# Sketchpad.net
KiCad netlist of a schematic drawn in EAGLE
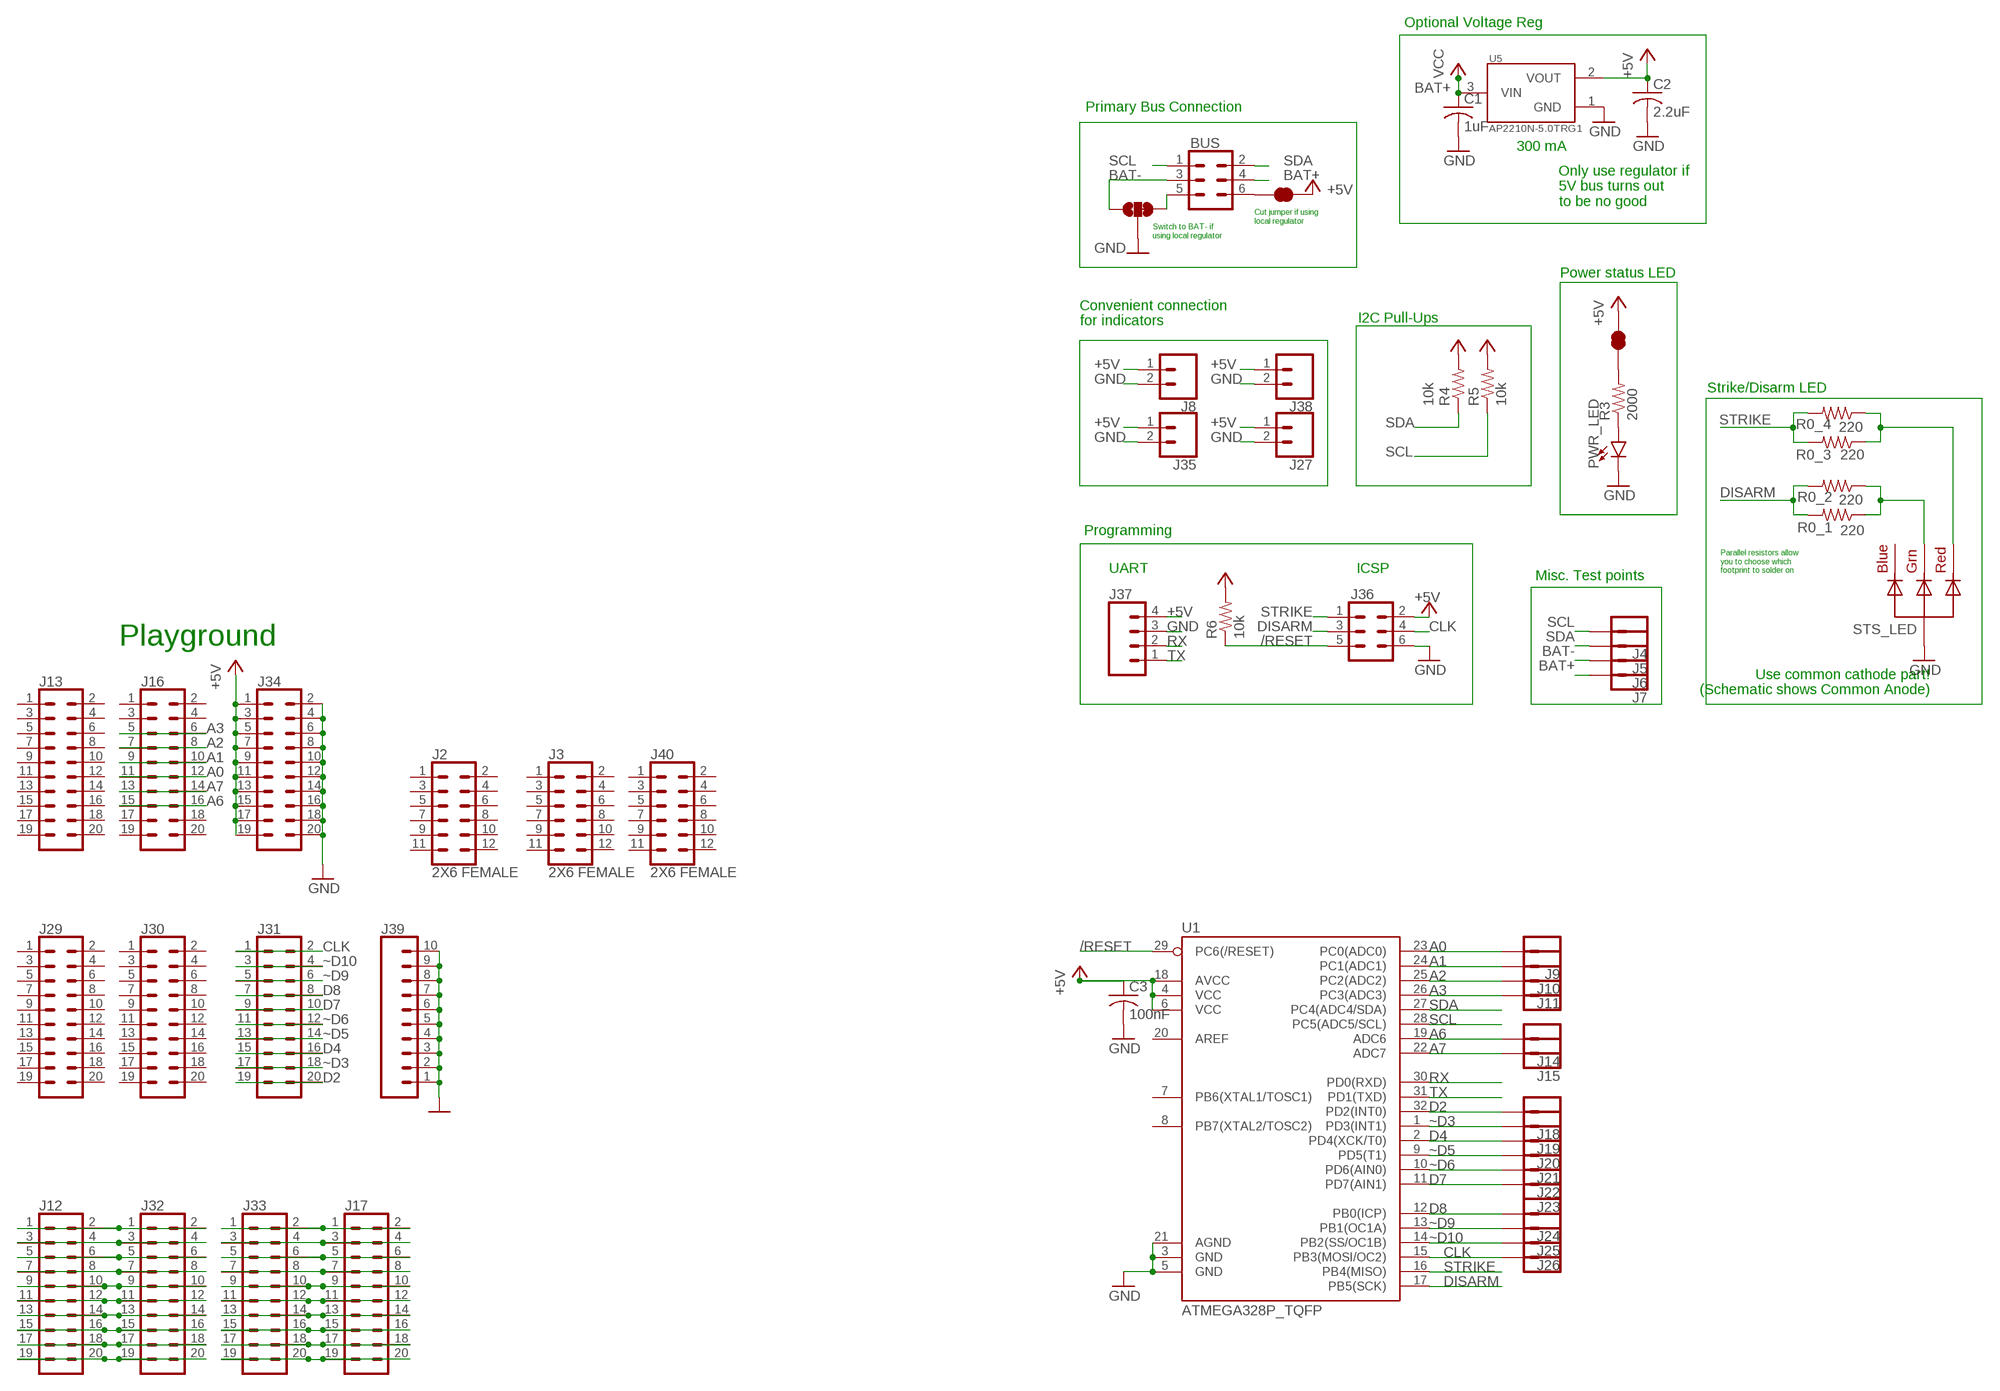
[diagram p0: schematic, sheet 1]

(export (version "E")
  (design (tool "Eeschema 10.0.6"))
  (components
    (comp (ref "BUS")
      (value "CONN_03X2SHROUD")
      (footprint "eagle-import:2X3-SHROUDED")
      (libsource (lib "eagle-import") (part "CONN_03X2SHROUD"))
    )
    (comp (ref "C1")
      (value "1uF")
      (footprint "eagle-import:C0805")
      (libsource (lib "eagle-import") (part "C-USC0805"))
    )
    (comp (ref "C2")
      (value "2.2uF")
      (footprint "eagle-import:C0805")
      (libsource (lib "eagle-import") (part "C-USC0805"))
    )
    (comp (ref "C3")
      (value "100nF")
      (footprint "eagle-import:C0805")
      (libsource (lib "eagle-import") (part "C-USC0805"))
    )
    (comp (ref "J1")
      (value "CONN_01")
      (footprint "eagle-import:1X01")
      (libsource (lib "eagle-import") (part "CONN_01"))
    )
    (comp (ref "J2")
      (value "2X6 FEMALE")
      (footprint "eagle-import:2X6")
      (libsource (lib "eagle-import") (part "CONN_06X2PTH_FEMALE"))
    )
    (comp (ref "J3")
      (value "2X6 FEMALE")
      (footprint "eagle-import:2X6")
      (libsource (lib "eagle-import") (part "CONN_06X2PTH_FEMALE"))
    )
    (comp (ref "J4")
      (value "CONN_01")
      (footprint "eagle-import:1X01")
      (libsource (lib "eagle-import") (part "CONN_01"))
    )
    (comp (ref "J5")
      (value "CONN_01")
      (footprint "eagle-import:1X01")
      (libsource (lib "eagle-import") (part "CONN_01"))
    )
    (comp (ref "J6")
      (value "CONN_01")
      (footprint "eagle-import:1X01")
      (libsource (lib "eagle-import") (part "CONN_01"))
    )
    (comp (ref "J7")
      (value "CONN_01")
      (footprint "eagle-import:1X01")
      (libsource (lib "eagle-import") (part "CONN_01"))
    )
    (comp (ref "J8")
      (value "CONN_02POLAR")
      (footprint "eagle-import:MOLEX-1X2")
      (libsource (lib "eagle-import") (part "CONN_02POLAR"))
    )
    (comp (ref "J9")
      (value "CONN_01")
      (footprint "eagle-import:1X01")
      (libsource (lib "eagle-import") (part "CONN_01"))
    )
    (comp (ref "J10")
      (value "CONN_01")
      (footprint "eagle-import:1X01")
      (libsource (lib "eagle-import") (part "CONN_01"))
    )
    (comp (ref "J11")
      (value "CONN_01")
      (footprint "eagle-import:1X01")
      (libsource (lib "eagle-import") (part "CONN_01"))
    )
    (comp (ref "J12")
      (value "CONN_10X2NOSILK")
      (footprint "eagle-import:2X10_NOSILK")
      (libsource (lib "eagle-import") (part "CONN_10X2NOSILK"))
    )
    (comp (ref "J13")
      (value "CONN_10X2NOSILK")
      (footprint "eagle-import:2X10_NOSILK")
      (libsource (lib "eagle-import") (part "CONN_10X2NOSILK"))
    )
    (comp (ref "J14")
      (value "CONN_01")
      (footprint "eagle-import:1X01")
      (libsource (lib "eagle-import") (part "CONN_01"))
    )
    (comp (ref "J15")
      (value "CONN_01")
      (footprint "eagle-import:1X01")
      (libsource (lib "eagle-import") (part "CONN_01"))
    )
    (comp (ref "J16")
      (value "CONN_10X2NOSILK")
      (footprint "eagle-import:2X10_NOSILK")
      (libsource (lib "eagle-import") (part "CONN_10X2NOSILK"))
    )
    (comp (ref "J17")
      (value "CONN_10X2NOSILK")
      (footprint "eagle-import:2X10_NOSILK")
      (libsource (lib "eagle-import") (part "CONN_10X2NOSILK"))
    )
    (comp (ref "J18")
      (value "CONN_01")
      (footprint "eagle-import:1X01")
      (libsource (lib "eagle-import") (part "CONN_01"))
    )
    (comp (ref "J19")
      (value "CONN_01")
      (footprint "eagle-import:1X01")
      (libsource (lib "eagle-import") (part "CONN_01"))
    )
    (comp (ref "J20")
      (value "CONN_01")
      (footprint "eagle-import:1X01")
      (libsource (lib "eagle-import") (part "CONN_01"))
    )
    (comp (ref "J21")
      (value "CONN_01")
      (footprint "eagle-import:1X01")
      (libsource (lib "eagle-import") (part "CONN_01"))
    )
    (comp (ref "J22")
      (value "CONN_01")
      (footprint "eagle-import:1X01")
      (libsource (lib "eagle-import") (part "CONN_01"))
    )
    (comp (ref "J23")
      (value "CONN_01")
      (footprint "eagle-import:1X01")
      (libsource (lib "eagle-import") (part "CONN_01"))
    )
    (comp (ref "J24")
      (value "CONN_01")
      (footprint "eagle-import:1X01")
      (libsource (lib "eagle-import") (part "CONN_01"))
    )
    (comp (ref "J25")
      (value "CONN_01")
      (footprint "eagle-import:1X01")
      (libsource (lib "eagle-import") (part "CONN_01"))
    )
    (comp (ref "J26")
      (value "CONN_01")
      (footprint "eagle-import:1X01")
      (libsource (lib "eagle-import") (part "CONN_01"))
    )
    (comp (ref "J27")
      (value "CONN_02POLAR")
      (footprint "eagle-import:MOLEX-1X2")
      (libsource (lib "eagle-import") (part "CONN_02POLAR"))
    )
    (comp (ref "J28")
      (value "CONN_01")
      (footprint "eagle-import:1X01")
      (libsource (lib "eagle-import") (part "CONN_01"))
    )
    (comp (ref "J29")
      (value "CONN_10X2NOSILK")
      (footprint "eagle-import:2X10_NOSILK")
      (libsource (lib "eagle-import") (part "CONN_10X2NOSILK"))
    )
    (comp (ref "J30")
      (value "CONN_10X2NOSILK")
      (footprint "eagle-import:2X10_NOSILK")
      (libsource (lib "eagle-import") (part "CONN_10X2NOSILK"))
    )
    (comp (ref "J31")
      (value "CONN_10X2NOSILK")
      (footprint "eagle-import:2X10_NOSILK")
      (libsource (lib "eagle-import") (part "CONN_10X2NOSILK"))
    )
    (comp (ref "J32")
      (value "CONN_10X2NOSILK")
      (footprint "eagle-import:2X10_NOSILK")
      (libsource (lib "eagle-import") (part "CONN_10X2NOSILK"))
    )
    (comp (ref "J33")
      (value "CONN_10X2NOSILK")
      (footprint "eagle-import:2X10_NOSILK")
      (libsource (lib "eagle-import") (part "CONN_10X2NOSILK"))
    )
    (comp (ref "J34")
      (value "CONN_10X2NOSILK")
      (footprint "eagle-import:2X10_NOSILK")
      (libsource (lib "eagle-import") (part "CONN_10X2NOSILK"))
    )
    (comp (ref "J35")
      (value "CONN_02POLAR")
      (footprint "eagle-import:MOLEX-1X2")
      (libsource (lib "eagle-import") (part "CONN_02POLAR"))
    )
    (comp (ref "J36")
      (value "CONN_03X22X3_SILK_MALE_PTH")
      (footprint "eagle-import:2X3")
      (libsource (lib "eagle-import") (part "CONN_03X22X3_SILK_MALE_PTH"))
    )
    (comp (ref "J37")
      (value "CONN_04")
      (footprint "eagle-import:1X04")
      (libsource (lib "eagle-import") (part "CONN_04"))
    )
    (comp (ref "J38")
      (value "CONN_02POLAR")
      (footprint "eagle-import:MOLEX-1X2")
      (libsource (lib "eagle-import") (part "CONN_02POLAR"))
    )
    (comp (ref "J39")
      (value "CONN_10NO_SILK_PTH_FEMALE")
      (footprint "eagle-import:1X10_NO_SILK")
      (libsource (lib "eagle-import") (part "CONN_10NO_SILK_PTH_FEMALE"))
    )
    (comp (ref "J40")
      (value "2X6 FEMALE")
      (footprint "eagle-import:2X6")
      (libsource (lib "eagle-import") (part "CONN_06X2PTH_FEMALE"))
    )
    (comp (ref "JP1")
      (value "JUMPER-SMT_2_NC_TRACE_SILK")
      (footprint "eagle-import:SMT-JUMPER_2_NC_TRACE_SILK")
      (libsource (lib "eagle-import") (part "JUMPER-SMT_2_NC_TRACE_SILK"))
    )
    (comp (ref "JP2")
      (value "JUMPER-SMT_3_1-NC_TRACE_SILK")
      (footprint "eagle-import:SMT-JUMPER_3_1-NC_TRACE_SILK")
      (libsource (lib "eagle-import") (part "JUMPER-SMT_3_1-NC_TRACE_SILK"))
    )
    (comp (ref "JP3")
      (value "JUMPER-SMT_2_NC_TRACE_SILK")
      (footprint "eagle-import:SMT-JUMPER_2_NC_TRACE_SILK")
      (libsource (lib "eagle-import") (part "JUMPER-SMT_2_NC_TRACE_SILK"))
    )
    (comp (ref "PWR_LED")
      (value "LED3MM")
      (footprint "eagle-import:LED_3MM")
      (libsource (lib "eagle-import") (part "LED3MM"))
    )
    (comp (ref "R0_1")
      (value "220")
      (footprint "eagle-import:0204_7")
      (libsource (lib "eagle-import") (part "R-US_0204/7"))
    )
    (comp (ref "R0_2")
      (value "220")
      (footprint "eagle-import:R0805")
      (libsource (lib "eagle-import") (part "R-US_R0805"))
    )
    (comp (ref "R0_3")
      (value "220")
      (footprint "eagle-import:0204_7")
      (libsource (lib "eagle-import") (part "R-US_0204/7"))
    )
    (comp (ref "R0_4")
      (value "220")
      (footprint "eagle-import:R0805")
      (libsource (lib "eagle-import") (part "R-US_R0805"))
    )
    (comp (ref "R3")
      (value "2000")
      (footprint "eagle-import:0204_7")
      (libsource (lib "eagle-import") (part "R-US_0204/7"))
    )
    (comp (ref "R4")
      (value "10k")
      (footprint "eagle-import:0204_7")
      (libsource (lib "eagle-import") (part "R-US_0204/7"))
    )
    (comp (ref "R5")
      (value "10k")
      (footprint "eagle-import:0204_7")
      (libsource (lib "eagle-import") (part "R-US_0204/7"))
    )
    (comp (ref "R6")
      (value "10k")
      (footprint "eagle-import:0204_7")
      (libsource (lib "eagle-import") (part "R-US_0204/7"))
    )
    (comp (ref "STS_LED")
      (value "RGBLED_CA-5MM")
      (footprint "eagle-import:LED5MMRGB")
      (libsource (lib "eagle-import") (part "RGBLED_CA-5MM"))
    )
    (comp (ref "U1")
      (value "ATMEGA328P_TQFP")
      (footprint "eagle-import:TQFP32-08")
      (libsource (lib "eagle-import") (part "ATMEGA328P_TQFP"))
    )
    (comp (ref "U5")
      (value "AP2210N-5.0TRG1")
      (footprint "eagle-import:SOT95P280X145-3N")
      (fields
        (field (name "DIGI-KEY_PART_NUMBER") "AP2210N-5.0TRG1DICT-ND")
        (field (name "MF") "Diodes Inc.")
      )
      (libsource (lib "eagle-import") (part "AP2210N-5.0TRG1"))
    )
  )
  (nets
    (net (code "1") (name "+5V") (class "Default")
      (node (ref "C2") (pin "1") (pinfunction "1_1") (pintype "passive"))
      (node (ref "C3") (pin "1") (pinfunction "1_1") (pintype "passive"))
      (node (ref "J27") (pin "1") (pinfunction "1_1") (pintype "passive"))
      (node (ref "J34") (pin "1") (pinfunction "1_1") (pintype "passive"))
      (node (ref "J34") (pin "11") (pinfunction "11_11") (pintype "passive"))
      (node (ref "J34") (pin "13") (pinfunction "13_13") (pintype "passive"))
      (node (ref "J34") (pin "15") (pinfunction "15_15") (pintype "passive"))
      (node (ref "J34") (pin "17") (pinfunction "17_17") (pintype "passive"))
      (node (ref "J34") (pin "19") (pinfunction "19_19") (pintype "passive"))
      (node (ref "J34") (pin "3") (pinfunction "3_3") (pintype "passive"))
      (node (ref "J34") (pin "5") (pinfunction "5_5") (pintype "passive"))
      (node (ref "J34") (pin "7") (pinfunction "7_7") (pintype "passive"))
      (node (ref "J34") (pin "9") (pinfunction "9_9") (pintype "passive"))
      (node (ref "J35") (pin "1") (pinfunction "1_1") (pintype "passive"))
      (node (ref "J36") (pin "2") (pinfunction "2_2") (pintype "bidirectional"))
      (node (ref "J37") (pin "4") (pinfunction "4_4") (pintype "passive"))
      (node (ref "J38") (pin "1") (pinfunction "1_1") (pintype "passive"))
      (node (ref "J8") (pin "1") (pinfunction "1_1") (pintype "passive"))
      (node (ref "JP1") (pin "2") (pinfunction "2_2") (pintype "passive"))
      (node (ref "JP3") (pin "2") (pinfunction "2_2") (pintype "passive"))
      (node (ref "R4") (pin "2") (pinfunction "2_2") (pintype "passive"))
      (node (ref "R5") (pin "2") (pinfunction "2_2") (pintype "passive"))
      (node (ref "R6") (pin "2") (pinfunction "2_2") (pintype "passive"))
      (node (ref "U1") (pin "18") (pinfunction "AVCC_18") (pintype "bidirectional"))
      (node (ref "U1") (pin "4") (pinfunction "VCC_4") (pintype "bidirectional"))
      (node (ref "U1") (pin "6") (pinfunction "VCC_6") (pintype "bidirectional"))
      (node (ref "U5") (pin "2") (pinfunction "VOUT_2") (pintype "output"))
    )
    (net (code "2") (name "/A0") (class "Default")
      (node (ref "J16") (pin "11") (pinfunction "11_11") (pintype "passive"))
      (node (ref "J16") (pin "12") (pinfunction "12_12") (pintype "passive"))
      (node (ref "J9") (pin "1") (pinfunction "1_1") (pintype "passive"))
      (node (ref "U1") (pin "23") (pinfunction "PC0(ADC0)_23") (pintype "bidirectional"))
    )
    (net (code "3") (name "/A1") (class "Default")
      (node (ref "J10") (pin "1") (pinfunction "1_1") (pintype "passive"))
      (node (ref "J16") (pin "10") (pinfunction "10_10") (pintype "passive"))
      (node (ref "J16") (pin "9") (pinfunction "9_9") (pintype "passive"))
      (node (ref "U1") (pin "24") (pinfunction "PC1(ADC1)_24") (pintype "bidirectional"))
    )
    (net (code "4") (name "/A2") (class "Default")
      (node (ref "J11") (pin "1") (pinfunction "1_1") (pintype "passive"))
      (node (ref "J16") (pin "7") (pinfunction "7_7") (pintype "passive"))
      (node (ref "J16") (pin "8") (pinfunction "8_8") (pintype "passive"))
      (node (ref "U1") (pin "25") (pinfunction "PC2(ADC2)_25") (pintype "bidirectional"))
    )
    (net (code "5") (name "/A3") (class "Default")
      (node (ref "J16") (pin "5") (pinfunction "5_5") (pintype "passive"))
      (node (ref "J16") (pin "6") (pinfunction "6_6") (pintype "passive"))
      (node (ref "J28") (pin "1") (pinfunction "1_1") (pintype "passive"))
      (node (ref "U1") (pin "26") (pinfunction "PC3(ADC3)_26") (pintype "bidirectional"))
    )
    (net (code "6") (name "/A6") (class "Default")
      (node (ref "J14") (pin "1") (pinfunction "1_1") (pintype "passive"))
      (node (ref "J16") (pin "15") (pinfunction "15_15") (pintype "passive"))
      (node (ref "J16") (pin "16") (pinfunction "16_16") (pintype "passive"))
      (node (ref "U1") (pin "19") (pinfunction "ADC6_19") (pintype "bidirectional"))
    )
    (net (code "7") (name "/A7") (class "Default")
      (node (ref "J15") (pin "1") (pinfunction "1_1") (pintype "passive"))
      (node (ref "J16") (pin "13") (pinfunction "13_13") (pintype "passive"))
      (node (ref "J16") (pin "14") (pinfunction "14_14") (pintype "passive"))
      (node (ref "U1") (pin "22") (pinfunction "ADC7_22") (pintype "bidirectional"))
    )
    (net (code "8") (name "/BAT-") (class "Default")
      (node (ref "BUS") (pin "3") (pinfunction "3_3") (pintype "bidirectional"))
      (node (ref "J6") (pin "1") (pinfunction "1_1") (pintype "passive"))
      (node (ref "JP2") (pin "1") (pinfunction "1_1") (pintype "passive"))
    )
    (net (code "9") (name "/CLK") (class "Default")
      (node (ref "J1") (pin "1") (pinfunction "1_1") (pintype "passive"))
      (node (ref "J31") (pin "1") (pinfunction "1_1") (pintype "passive"))
      (node (ref "J31") (pin "2") (pinfunction "2_2") (pintype "passive"))
      (node (ref "J36") (pin "4") (pinfunction "4_4") (pintype "bidirectional"))
      (node (ref "U1") (pin "15") (pinfunction "PB3(MOSI/OC2)_15") (pintype "bidirectional"))
    )
    (net (code "10") (name "/D2") (class "Default")
      (node (ref "J18") (pin "1") (pinfunction "1_1") (pintype "passive"))
      (node (ref "J31") (pin "19") (pinfunction "19_19") (pintype "passive"))
      (node (ref "J31") (pin "20") (pinfunction "20_20") (pintype "passive"))
      (node (ref "U1") (pin "32") (pinfunction "PD2(INT0)_32") (pintype "bidirectional"))
    )
    (net (code "11") (name "/D4") (class "Default")
      (node (ref "J20") (pin "1") (pinfunction "1_1") (pintype "passive"))
      (node (ref "J31") (pin "15") (pinfunction "15_15") (pintype "passive"))
      (node (ref "J31") (pin "16") (pinfunction "16_16") (pintype "passive"))
      (node (ref "U1") (pin "2") (pinfunction "PD4(XCK/T0)_2") (pintype "bidirectional"))
    )
    (net (code "12") (name "/D7") (class "Default")
      (node (ref "J23") (pin "1") (pinfunction "1_1") (pintype "passive"))
      (node (ref "J31") (pin "10") (pinfunction "10_10") (pintype "passive"))
      (node (ref "J31") (pin "9") (pinfunction "9_9") (pintype "passive"))
      (node (ref "U1") (pin "11") (pinfunction "PD7(AIN1)_11") (pintype "bidirectional"))
    )
    (net (code "13") (name "/D8") (class "Default")
      (node (ref "J24") (pin "1") (pinfunction "1_1") (pintype "passive"))
      (node (ref "J31") (pin "7") (pinfunction "7_7") (pintype "passive"))
      (node (ref "J31") (pin "8") (pinfunction "8_8") (pintype "passive"))
      (node (ref "U1") (pin "12") (pinfunction "PB0(ICP)_12") (pintype "bidirectional"))
    )
    (net (code "14") (name "/DISARM") (class "Default")
      (node (ref "J36") (pin "3") (pinfunction "3_3") (pintype "bidirectional"))
      (node (ref "R0_1") (pin "2") (pinfunction "2_2") (pintype "passive"))
      (node (ref "R0_2") (pin "2") (pinfunction "2_2") (pintype "passive"))
      (node (ref "U1") (pin "17") (pinfunction "PB5(SCK)_17") (pintype "bidirectional"))
    )
    (net (code "15") (name "/RX") (class "Default")
      (node (ref "J37") (pin "2") (pinfunction "2_2") (pintype "passive"))
      (node (ref "U1") (pin "30") (pinfunction "PD0(RXD)_30") (pintype "bidirectional"))
    )
    (net (code "16") (name "/SCL") (class "Default")
      (node (ref "BUS") (pin "1") (pinfunction "1_1") (pintype "bidirectional"))
      (node (ref "J4") (pin "1") (pinfunction "1_1") (pintype "passive"))
      (node (ref "R5") (pin "1") (pinfunction "1_1") (pintype "passive"))
      (node (ref "U1") (pin "28") (pinfunction "PC5(ADC5/SCL)_28") (pintype "bidirectional"))
    )
    (net (code "17") (name "/SDA") (class "Default")
      (node (ref "BUS") (pin "2") (pinfunction "2_2") (pintype "bidirectional"))
      (node (ref "J5") (pin "1") (pinfunction "1_1") (pintype "passive"))
      (node (ref "R4") (pin "1") (pinfunction "1_1") (pintype "passive"))
      (node (ref "U1") (pin "27") (pinfunction "PC4(ADC4/SDA)_27") (pintype "bidirectional"))
    )
    (net (code "18") (name "/STRIKE") (class "Default")
      (node (ref "J36") (pin "1") (pinfunction "1_1") (pintype "bidirectional"))
      (node (ref "R0_3") (pin "2") (pinfunction "2_2") (pintype "passive"))
      (node (ref "R0_4") (pin "2") (pinfunction "2_2") (pintype "passive"))
      (node (ref "U1") (pin "16") (pinfunction "PB4(MISO)_16") (pintype "bidirectional"))
    )
    (net (code "19") (name "/TX") (class "Default")
      (node (ref "J37") (pin "1") (pinfunction "1_1") (pintype "passive"))
      (node (ref "U1") (pin "31") (pinfunction "PD1(TXD)_31") (pintype "bidirectional"))
    )
    (net (code "20") (name "/{slash}RESET") (class "Default")
      (node (ref "J36") (pin "5") (pinfunction "5_5") (pintype "bidirectional"))
      (node (ref "R6") (pin "1") (pinfunction "1_1") (pintype "passive"))
      (node (ref "U1") (pin "29") (pinfunction "PC6(/RESET)_29") (pintype "bidirectional"))
    )
    (net (code "21") (name "/~{D3}") (class "Default")
      (node (ref "J19") (pin "1") (pinfunction "1_1") (pintype "passive"))
      (node (ref "J31") (pin "17") (pinfunction "17_17") (pintype "passive"))
      (node (ref "J31") (pin "18") (pinfunction "18_18") (pintype "passive"))
      (node (ref "U1") (pin "1") (pinfunction "PD3(INT1)_1") (pintype "bidirectional"))
    )
    (net (code "22") (name "/~{D5}") (class "Default")
      (node (ref "J21") (pin "1") (pinfunction "1_1") (pintype "passive"))
      (node (ref "J31") (pin "13") (pinfunction "13_13") (pintype "passive"))
      (node (ref "J31") (pin "14") (pinfunction "14_14") (pintype "passive"))
      (node (ref "U1") (pin "9") (pinfunction "PD5(T1)_9") (pintype "bidirectional"))
    )
    (net (code "23") (name "/~{D6}") (class "Default")
      (node (ref "J22") (pin "1") (pinfunction "1_1") (pintype "passive"))
      (node (ref "J31") (pin "11") (pinfunction "11_11") (pintype "passive"))
      (node (ref "J31") (pin "12") (pinfunction "12_12") (pintype "passive"))
      (node (ref "U1") (pin "10") (pinfunction "PD6(AIN0)_10") (pintype "bidirectional"))
    )
    (net (code "24") (name "/~{D9}") (class "Default")
      (node (ref "J25") (pin "1") (pinfunction "1_1") (pintype "passive"))
      (node (ref "J31") (pin "5") (pinfunction "5_5") (pintype "passive"))
      (node (ref "J31") (pin "6") (pinfunction "6_6") (pintype "passive"))
      (node (ref "U1") (pin "13") (pinfunction "PB1(OC1A)_13") (pintype "bidirectional"))
    )
    (net (code "25") (name "/~{D10}") (class "Default")
      (node (ref "J26") (pin "1") (pinfunction "1_1") (pintype "passive"))
      (node (ref "J31") (pin "3") (pinfunction "3_3") (pintype "passive"))
      (node (ref "J31") (pin "4") (pinfunction "4_4") (pintype "passive"))
      (node (ref "U1") (pin "14") (pinfunction "PB2(SS/OC1B)_14") (pintype "bidirectional"))
    )
    (net (code "26") (name "GND") (class "Default")
      (node (ref "C1") (pin "2") (pinfunction "2_2") (pintype "passive"))
      (node (ref "C2") (pin "2") (pinfunction "2_2") (pintype "passive"))
      (node (ref "C3") (pin "2") (pinfunction "2_2") (pintype "passive"))
      (node (ref "J27") (pin "2") (pinfunction "2_2") (pintype "passive"))
      (node (ref "J34") (pin "10") (pinfunction "10_10") (pintype "passive"))
      (node (ref "J34") (pin "12") (pinfunction "12_12") (pintype "passive"))
      (node (ref "J34") (pin "14") (pinfunction "14_14") (pintype "passive"))
      (node (ref "J34") (pin "16") (pinfunction "16_16") (pintype "passive"))
      (node (ref "J34") (pin "18") (pinfunction "18_18") (pintype "passive"))
      (node (ref "J34") (pin "2") (pinfunction "2_2") (pintype "passive"))
      (node (ref "J34") (pin "20") (pinfunction "20_20") (pintype "passive"))
      (node (ref "J34") (pin "4") (pinfunction "4_4") (pintype "passive"))
      (node (ref "J34") (pin "6") (pinfunction "6_6") (pintype "passive"))
      (node (ref "J34") (pin "8") (pinfunction "8_8") (pintype "passive"))
      (node (ref "J35") (pin "2") (pinfunction "2_2") (pintype "passive"))
      (node (ref "J36") (pin "6") (pinfunction "6_6") (pintype "bidirectional"))
      (node (ref "J37") (pin "3") (pinfunction "3_3") (pintype "passive"))
      (node (ref "J38") (pin "2") (pinfunction "2_2") (pintype "passive"))
      (node (ref "J39") (pin "1") (pinfunction "1_1") (pintype "passive"))
      (node (ref "J39") (pin "10") (pinfunction "10_10") (pintype "passive"))
      (node (ref "J39") (pin "2") (pinfunction "2_2") (pintype "passive"))
      (node (ref "J39") (pin "3") (pinfunction "3_3") (pintype "passive"))
      (node (ref "J39") (pin "4") (pinfunction "4_4") (pintype "passive"))
      (node (ref "J39") (pin "5") (pinfunction "5_5") (pintype "passive"))
      (node (ref "J39") (pin "6") (pinfunction "6_6") (pintype "passive"))
      (node (ref "J39") (pin "7") (pinfunction "7_7") (pintype "passive"))
      (node (ref "J39") (pin "8") (pinfunction "8_8") (pintype "passive"))
      (node (ref "J39") (pin "9") (pinfunction "9_9") (pintype "passive"))
      (node (ref "J8") (pin "2") (pinfunction "2_2") (pintype "passive"))
      (node (ref "JP2") (pin "2") (pinfunction "2_2") (pintype "passive"))
      (node (ref "PWR_LED") (pin "K") (pinfunction "C_K") (pintype "passive"))
      (node (ref "STS_LED") (pin "2") (pinfunction "VCC_2") (pintype "bidirectional"))
      (node (ref "U1") (pin "21") (pinfunction "AGND_21") (pintype "bidirectional"))
      (node (ref "U1") (pin "3") (pinfunction "GND_3") (pintype "bidirectional"))
      (node (ref "U1") (pin "5") (pinfunction "GND_5") (pintype "bidirectional"))
      (node (ref "U5") (pin "1") (pinfunction "GND_1") (pintype "power_in"))
    )
    (net (code "27") (name "Net-(BUS-Pad5)") (class "Default")
      (node (ref "BUS") (pin "5") (pinfunction "5_5") (pintype "bidirectional"))
      (node (ref "JP2") (pin "3") (pinfunction "3_3") (pintype "passive"))
    )
    (net (code "28") (name "Net-(BUS-Pad6)") (class "Default")
      (node (ref "BUS") (pin "6") (pinfunction "6_6") (pintype "bidirectional"))
      (node (ref "JP1") (pin "1") (pinfunction "1_1") (pintype "passive"))
    )
    (net (code "29") (name "Net-(J12-Pad1)") (class "Default")
      (node (ref "J12") (pin "1") (pinfunction "1_1") (pintype "passive"))
      (node (ref "J12") (pin "2") (pinfunction "2_2") (pintype "passive"))
      (node (ref "J32") (pin "1") (pinfunction "1_1") (pintype "passive"))
      (node (ref "J32") (pin "2") (pinfunction "2_2") (pintype "passive"))
    )
    (net (code "30") (name "Net-(J12-Pad3)") (class "Default")
      (node (ref "J12") (pin "3") (pinfunction "3_3") (pintype "passive"))
      (node (ref "J12") (pin "4") (pinfunction "4_4") (pintype "passive"))
      (node (ref "J32") (pin "3") (pinfunction "3_3") (pintype "passive"))
      (node (ref "J32") (pin "4") (pinfunction "4_4") (pintype "passive"))
    )
    (net (code "31") (name "Net-(J12-Pad5)") (class "Default")
      (node (ref "J12") (pin "5") (pinfunction "5_5") (pintype "passive"))
      (node (ref "J12") (pin "6") (pinfunction "6_6") (pintype "passive"))
      (node (ref "J32") (pin "5") (pinfunction "5_5") (pintype "passive"))
      (node (ref "J32") (pin "6") (pinfunction "6_6") (pintype "passive"))
    )
    (net (code "32") (name "Net-(J12-Pad7)") (class "Default")
      (node (ref "J12") (pin "7") (pinfunction "7_7") (pintype "passive"))
      (node (ref "J12") (pin "8") (pinfunction "8_8") (pintype "passive"))
      (node (ref "J32") (pin "7") (pinfunction "7_7") (pintype "passive"))
      (node (ref "J32") (pin "8") (pinfunction "8_8") (pintype "passive"))
    )
    (net (code "33") (name "Net-(J12-Pad10)") (class "Default")
      (node (ref "J12") (pin "10") (pinfunction "10_10") (pintype "passive"))
      (node (ref "J12") (pin "9") (pinfunction "9_9") (pintype "passive"))
      (node (ref "J32") (pin "10") (pinfunction "10_10") (pintype "passive"))
      (node (ref "J32") (pin "9") (pinfunction "9_9") (pintype "passive"))
    )
    (net (code "34") (name "Net-(J12-Pad11)") (class "Default")
      (node (ref "J12") (pin "11") (pinfunction "11_11") (pintype "passive"))
      (node (ref "J12") (pin "12") (pinfunction "12_12") (pintype "passive"))
      (node (ref "J32") (pin "11") (pinfunction "11_11") (pintype "passive"))
      (node (ref "J32") (pin "12") (pinfunction "12_12") (pintype "passive"))
    )
    (net (code "35") (name "Net-(J12-Pad13)") (class "Default")
      (node (ref "J12") (pin "13") (pinfunction "13_13") (pintype "passive"))
      (node (ref "J12") (pin "14") (pinfunction "14_14") (pintype "passive"))
      (node (ref "J32") (pin "13") (pinfunction "13_13") (pintype "passive"))
      (node (ref "J32") (pin "14") (pinfunction "14_14") (pintype "passive"))
    )
    (net (code "36") (name "Net-(J12-Pad15)") (class "Default")
      (node (ref "J12") (pin "15") (pinfunction "15_15") (pintype "passive"))
      (node (ref "J12") (pin "16") (pinfunction "16_16") (pintype "passive"))
      (node (ref "J32") (pin "15") (pinfunction "15_15") (pintype "passive"))
      (node (ref "J32") (pin "16") (pinfunction "16_16") (pintype "passive"))
    )
    (net (code "37") (name "Net-(J12-Pad17)") (class "Default")
      (node (ref "J12") (pin "17") (pinfunction "17_17") (pintype "passive"))
      (node (ref "J12") (pin "18") (pinfunction "18_18") (pintype "passive"))
      (node (ref "J32") (pin "17") (pinfunction "17_17") (pintype "passive"))
      (node (ref "J32") (pin "18") (pinfunction "18_18") (pintype "passive"))
    )
    (net (code "38") (name "Net-(J12-Pad19)") (class "Default")
      (node (ref "J12") (pin "19") (pinfunction "19_19") (pintype "passive"))
      (node (ref "J12") (pin "20") (pinfunction "20_20") (pintype "passive"))
      (node (ref "J32") (pin "19") (pinfunction "19_19") (pintype "passive"))
      (node (ref "J32") (pin "20") (pinfunction "20_20") (pintype "passive"))
    )
    (net (code "39") (name "Net-(J17-Pad1)") (class "Default")
      (node (ref "J17") (pin "1") (pinfunction "1_1") (pintype "passive"))
      (node (ref "J17") (pin "2") (pinfunction "2_2") (pintype "passive"))
      (node (ref "J33") (pin "1") (pinfunction "1_1") (pintype "passive"))
      (node (ref "J33") (pin "2") (pinfunction "2_2") (pintype "passive"))
    )
    (net (code "40") (name "Net-(J17-Pad3)") (class "Default")
      (node (ref "J17") (pin "3") (pinfunction "3_3") (pintype "passive"))
      (node (ref "J17") (pin "4") (pinfunction "4_4") (pintype "passive"))
      (node (ref "J33") (pin "3") (pinfunction "3_3") (pintype "passive"))
      (node (ref "J33") (pin "4") (pinfunction "4_4") (pintype "passive"))
    )
    (net (code "41") (name "Net-(J17-Pad5)") (class "Default")
      (node (ref "J17") (pin "5") (pinfunction "5_5") (pintype "passive"))
      (node (ref "J17") (pin "6") (pinfunction "6_6") (pintype "passive"))
      (node (ref "J33") (pin "5") (pinfunction "5_5") (pintype "passive"))
      (node (ref "J33") (pin "6") (pinfunction "6_6") (pintype "passive"))
    )
    (net (code "42") (name "Net-(J17-Pad7)") (class "Default")
      (node (ref "J17") (pin "7") (pinfunction "7_7") (pintype "passive"))
      (node (ref "J17") (pin "8") (pinfunction "8_8") (pintype "passive"))
      (node (ref "J33") (pin "7") (pinfunction "7_7") (pintype "passive"))
      (node (ref "J33") (pin "8") (pinfunction "8_8") (pintype "passive"))
    )
    (net (code "43") (name "Net-(J17-Pad10)") (class "Default")
      (node (ref "J17") (pin "10") (pinfunction "10_10") (pintype "passive"))
      (node (ref "J17") (pin "9") (pinfunction "9_9") (pintype "passive"))
      (node (ref "J33") (pin "10") (pinfunction "10_10") (pintype "passive"))
      (node (ref "J33") (pin "9") (pinfunction "9_9") (pintype "passive"))
    )
    (net (code "44") (name "Net-(J17-Pad11)") (class "Default")
      (node (ref "J17") (pin "11") (pinfunction "11_11") (pintype "passive"))
      (node (ref "J17") (pin "12") (pinfunction "12_12") (pintype "passive"))
      (node (ref "J33") (pin "11") (pinfunction "11_11") (pintype "passive"))
      (node (ref "J33") (pin "12") (pinfunction "12_12") (pintype "passive"))
    )
    (net (code "45") (name "Net-(J17-Pad13)") (class "Default")
      (node (ref "J17") (pin "13") (pinfunction "13_13") (pintype "passive"))
      (node (ref "J17") (pin "14") (pinfunction "14_14") (pintype "passive"))
      (node (ref "J33") (pin "13") (pinfunction "13_13") (pintype "passive"))
      (node (ref "J33") (pin "14") (pinfunction "14_14") (pintype "passive"))
    )
    (net (code "46") (name "Net-(J17-Pad15)") (class "Default")
      (node (ref "J17") (pin "15") (pinfunction "15_15") (pintype "passive"))
      (node (ref "J17") (pin "16") (pinfunction "16_16") (pintype "passive"))
      (node (ref "J33") (pin "15") (pinfunction "15_15") (pintype "passive"))
      (node (ref "J33") (pin "16") (pinfunction "16_16") (pintype "passive"))
    )
    (net (code "47") (name "Net-(J17-Pad17)") (class "Default")
      (node (ref "J17") (pin "17") (pinfunction "17_17") (pintype "passive"))
      (node (ref "J17") (pin "18") (pinfunction "18_18") (pintype "passive"))
      (node (ref "J33") (pin "17") (pinfunction "17_17") (pintype "passive"))
      (node (ref "J33") (pin "18") (pinfunction "18_18") (pintype "passive"))
    )
    (net (code "48") (name "Net-(J17-Pad19)") (class "Default")
      (node (ref "J17") (pin "19") (pinfunction "19_19") (pintype "passive"))
      (node (ref "J17") (pin "20") (pinfunction "20_20") (pintype "passive"))
      (node (ref "J33") (pin "19") (pinfunction "19_19") (pintype "passive"))
      (node (ref "J33") (pin "20") (pinfunction "20_20") (pintype "passive"))
    )
    (net (code "49") (name "Net-(JP3-Pad1)") (class "Default")
      (node (ref "JP3") (pin "1") (pinfunction "1_1") (pintype "passive"))
      (node (ref "R3") (pin "2") (pinfunction "2_2") (pintype "passive"))
    )
    (net (code "50") (name "Net-(PWR_LED-PadA)") (class "Default")
      (node (ref "PWR_LED") (pin "A") (pinfunction "A_A") (pintype "passive"))
      (node (ref "R3") (pin "1") (pinfunction "1_1") (pintype "passive"))
    )
    (net (code "51") (name "Net-(STS_LED-GREEN)") (class "Default")
      (node (ref "R0_1") (pin "1") (pinfunction "1_1") (pintype "passive"))
      (node (ref "R0_2") (pin "1") (pinfunction "1_1") (pintype "passive"))
      (node (ref "STS_LED") (pin "3") (pinfunction "GREEN_3") (pintype "bidirectional"))
    )
    (net (code "52") (name "Net-(STS_LED-RED)") (class "Default")
      (node (ref "R0_3") (pin "1") (pinfunction "1_1") (pintype "passive"))
      (node (ref "R0_4") (pin "1") (pinfunction "1_1") (pintype "passive"))
      (node (ref "STS_LED") (pin "1") (pinfunction "RED_1") (pintype "bidirectional"))
    )
    (net (code "53") (name "VCC") (class "Default")
      (node (ref "BUS") (pin "4") (pinfunction "4_4") (pintype "bidirectional"))
      (node (ref "C1") (pin "1") (pinfunction "1_1") (pintype "passive"))
      (node (ref "J7") (pin "1") (pinfunction "1_1") (pintype "passive"))
      (node (ref "U5") (pin "3") (pinfunction "VIN_3") (pintype "input"))
    )
    (net (code "54") (name "unconnected-(J2-Pad1)") (class "Default")
      (node (ref "J2") (pin "1") (pinfunction "1_1") (pintype "passive"))
    )
    (net (code "55") (name "unconnected-(J2-Pad2)") (class "Default")
      (node (ref "J2") (pin "2") (pinfunction "2_2") (pintype "passive"))
    )
    (net (code "56") (name "unconnected-(J2-Pad3)") (class "Default")
      (node (ref "J2") (pin "3") (pinfunction "3_3") (pintype "passive"))
    )
    (net (code "57") (name "unconnected-(J2-Pad4)") (class "Default")
      (node (ref "J2") (pin "4") (pinfunction "4_4") (pintype "passive"))
    )
    (net (code "58") (name "unconnected-(J2-Pad5)") (class "Default")
      (node (ref "J2") (pin "5") (pinfunction "5_5") (pintype "passive"))
    )
    (net (code "59") (name "unconnected-(J2-Pad6)") (class "Default")
      (node (ref "J2") (pin "6") (pinfunction "6_6") (pintype "passive"))
    )
    (net (code "60") (name "unconnected-(J2-Pad7)") (class "Default")
      (node (ref "J2") (pin "7") (pinfunction "7_7") (pintype "passive"))
    )
    (net (code "61") (name "unconnected-(J2-Pad8)") (class "Default")
      (node (ref "J2") (pin "8") (pinfunction "8_8") (pintype "passive"))
    )
    (net (code "62") (name "unconnected-(J2-Pad9)") (class "Default")
      (node (ref "J2") (pin "9") (pinfunction "9_9") (pintype "passive"))
    )
    (net (code "63") (name "unconnected-(J2-Pad10)") (class "Default")
      (node (ref "J2") (pin "10") (pinfunction "10_10") (pintype "passive"))
    )
    (net (code "64") (name "unconnected-(J2-Pad11)") (class "Default")
      (node (ref "J2") (pin "11") (pinfunction "11_11") (pintype "passive"))
    )
    (net (code "65") (name "unconnected-(J2-Pad12)") (class "Default")
      (node (ref "J2") (pin "12") (pinfunction "12_12") (pintype "passive"))
    )
    (net (code "66") (name "unconnected-(J3-Pad1)") (class "Default")
      (node (ref "J3") (pin "1") (pinfunction "1_1") (pintype "passive"))
    )
    (net (code "67") (name "unconnected-(J3-Pad2)") (class "Default")
      (node (ref "J3") (pin "2") (pinfunction "2_2") (pintype "passive"))
    )
    (net (code "68") (name "unconnected-(J3-Pad3)") (class "Default")
      (node (ref "J3") (pin "3") (pinfunction "3_3") (pintype "passive"))
    )
    (net (code "69") (name "unconnected-(J3-Pad4)") (class "Default")
      (node (ref "J3") (pin "4") (pinfunction "4_4") (pintype "passive"))
    )
    (net (code "70") (name "unconnected-(J3-Pad5)") (class "Default")
      (node (ref "J3") (pin "5") (pinfunction "5_5") (pintype "passive"))
    )
    (net (code "71") (name "unconnected-(J3-Pad6)") (class "Default")
      (node (ref "J3") (pin "6") (pinfunction "6_6") (pintype "passive"))
    )
    (net (code "72") (name "unconnected-(J3-Pad7)") (class "Default")
      (node (ref "J3") (pin "7") (pinfunction "7_7") (pintype "passive"))
    )
    (net (code "73") (name "unconnected-(J3-Pad8)") (class "Default")
      (node (ref "J3") (pin "8") (pinfunction "8_8") (pintype "passive"))
    )
    (net (code "74") (name "unconnected-(J3-Pad9)") (class "Default")
      (node (ref "J3") (pin "9") (pinfunction "9_9") (pintype "passive"))
    )
    (net (code "75") (name "unconnected-(J3-Pad10)") (class "Default")
      (node (ref "J3") (pin "10") (pinfunction "10_10") (pintype "passive"))
    )
    (net (code "76") (name "unconnected-(J3-Pad11)") (class "Default")
      (node (ref "J3") (pin "11") (pinfunction "11_11") (pintype "passive"))
    )
    (net (code "77") (name "unconnected-(J3-Pad12)") (class "Default")
      (node (ref "J3") (pin "12") (pinfunction "12_12") (pintype "passive"))
    )
    (net (code "78") (name "unconnected-(J13-Pad1)") (class "Default")
      (node (ref "J13") (pin "1") (pinfunction "1_1") (pintype "passive"))
    )
    (net (code "79") (name "unconnected-(J13-Pad2)") (class "Default")
      (node (ref "J13") (pin "2") (pinfunction "2_2") (pintype "passive"))
    )
    (net (code "80") (name "unconnected-(J13-Pad3)") (class "Default")
      (node (ref "J13") (pin "3") (pinfunction "3_3") (pintype "passive"))
    )
    (net (code "81") (name "unconnected-(J13-Pad4)") (class "Default")
      (node (ref "J13") (pin "4") (pinfunction "4_4") (pintype "passive"))
    )
    (net (code "82") (name "unconnected-(J13-Pad5)") (class "Default")
      (node (ref "J13") (pin "5") (pinfunction "5_5") (pintype "passive"))
    )
    (net (code "83") (name "unconnected-(J13-Pad6)") (class "Default")
      (node (ref "J13") (pin "6") (pinfunction "6_6") (pintype "passive"))
    )
    (net (code "84") (name "unconnected-(J13-Pad7)") (class "Default")
      (node (ref "J13") (pin "7") (pinfunction "7_7") (pintype "passive"))
    )
    (net (code "85") (name "unconnected-(J13-Pad8)") (class "Default")
      (node (ref "J13") (pin "8") (pinfunction "8_8") (pintype "passive"))
    )
    (net (code "86") (name "unconnected-(J13-Pad9)") (class "Default")
      (node (ref "J13") (pin "9") (pinfunction "9_9") (pintype "passive"))
    )
    (net (code "87") (name "unconnected-(J13-Pad10)") (class "Default")
      (node (ref "J13") (pin "10") (pinfunction "10_10") (pintype "passive"))
    )
    (net (code "88") (name "unconnected-(J13-Pad11)") (class "Default")
      (node (ref "J13") (pin "11") (pinfunction "11_11") (pintype "passive"))
    )
    (net (code "89") (name "unconnected-(J13-Pad12)") (class "Default")
      (node (ref "J13") (pin "12") (pinfunction "12_12") (pintype "passive"))
    )
    (net (code "90") (name "unconnected-(J13-Pad13)") (class "Default")
      (node (ref "J13") (pin "13") (pinfunction "13_13") (pintype "passive"))
    )
    (net (code "91") (name "unconnected-(J13-Pad14)") (class "Default")
      (node (ref "J13") (pin "14") (pinfunction "14_14") (pintype "passive"))
    )
    (net (code "92") (name "unconnected-(J13-Pad15)") (class "Default")
      (node (ref "J13") (pin "15") (pinfunction "15_15") (pintype "passive"))
    )
    (net (code "93") (name "unconnected-(J13-Pad16)") (class "Default")
      (node (ref "J13") (pin "16") (pinfunction "16_16") (pintype "passive"))
    )
    (net (code "94") (name "unconnected-(J13-Pad17)") (class "Default")
      (node (ref "J13") (pin "17") (pinfunction "17_17") (pintype "passive"))
    )
    (net (code "95") (name "unconnected-(J13-Pad18)") (class "Default")
      (node (ref "J13") (pin "18") (pinfunction "18_18") (pintype "passive"))
    )
    (net (code "96") (name "unconnected-(J13-Pad19)") (class "Default")
      (node (ref "J13") (pin "19") (pinfunction "19_19") (pintype "passive"))
    )
    (net (code "97") (name "unconnected-(J13-Pad20)") (class "Default")
      (node (ref "J13") (pin "20") (pinfunction "20_20") (pintype "passive"))
    )
    (net (code "98") (name "unconnected-(J16-Pad1)") (class "Default")
      (node (ref "J16") (pin "1") (pinfunction "1_1") (pintype "passive"))
    )
    (net (code "99") (name "unconnected-(J16-Pad2)") (class "Default")
      (node (ref "J16") (pin "2") (pinfunction "2_2") (pintype "passive"))
    )
    (net (code "100") (name "unconnected-(J16-Pad3)") (class "Default")
      (node (ref "J16") (pin "3") (pinfunction "3_3") (pintype "passive"))
    )
    (net (code "101") (name "unconnected-(J16-Pad4)") (class "Default")
      (node (ref "J16") (pin "4") (pinfunction "4_4") (pintype "passive"))
    )
    (net (code "102") (name "unconnected-(J16-Pad17)") (class "Default")
      (node (ref "J16") (pin "17") (pinfunction "17_17") (pintype "passive"))
    )
    (net (code "103") (name "unconnected-(J16-Pad18)") (class "Default")
      (node (ref "J16") (pin "18") (pinfunction "18_18") (pintype "passive"))
    )
    (net (code "104") (name "unconnected-(J16-Pad19)") (class "Default")
      (node (ref "J16") (pin "19") (pinfunction "19_19") (pintype "passive"))
    )
    (net (code "105") (name "unconnected-(J16-Pad20)") (class "Default")
      (node (ref "J16") (pin "20") (pinfunction "20_20") (pintype "passive"))
    )
    (net (code "106") (name "unconnected-(J29-Pad1)") (class "Default")
      (node (ref "J29") (pin "1") (pinfunction "1_1") (pintype "passive"))
    )
    (net (code "107") (name "unconnected-(J29-Pad2)") (class "Default")
      (node (ref "J29") (pin "2") (pinfunction "2_2") (pintype "passive"))
    )
    (net (code "108") (name "unconnected-(J29-Pad3)") (class "Default")
      (node (ref "J29") (pin "3") (pinfunction "3_3") (pintype "passive"))
    )
    (net (code "109") (name "unconnected-(J29-Pad4)") (class "Default")
      (node (ref "J29") (pin "4") (pinfunction "4_4") (pintype "passive"))
    )
    (net (code "110") (name "unconnected-(J29-Pad5)") (class "Default")
      (node (ref "J29") (pin "5") (pinfunction "5_5") (pintype "passive"))
    )
    (net (code "111") (name "unconnected-(J29-Pad6)") (class "Default")
      (node (ref "J29") (pin "6") (pinfunction "6_6") (pintype "passive"))
    )
    (net (code "112") (name "unconnected-(J29-Pad7)") (class "Default")
      (node (ref "J29") (pin "7") (pinfunction "7_7") (pintype "passive"))
    )
    (net (code "113") (name "unconnected-(J29-Pad8)") (class "Default")
      (node (ref "J29") (pin "8") (pinfunction "8_8") (pintype "passive"))
    )
    (net (code "114") (name "unconnected-(J29-Pad9)") (class "Default")
      (node (ref "J29") (pin "9") (pinfunction "9_9") (pintype "passive"))
    )
    (net (code "115") (name "unconnected-(J29-Pad10)") (class "Default")
      (node (ref "J29") (pin "10") (pinfunction "10_10") (pintype "passive"))
    )
    (net (code "116") (name "unconnected-(J29-Pad11)") (class "Default")
      (node (ref "J29") (pin "11") (pinfunction "11_11") (pintype "passive"))
    )
    (net (code "117") (name "unconnected-(J29-Pad12)") (class "Default")
      (node (ref "J29") (pin "12") (pinfunction "12_12") (pintype "passive"))
    )
    (net (code "118") (name "unconnected-(J29-Pad13)") (class "Default")
      (node (ref "J29") (pin "13") (pinfunction "13_13") (pintype "passive"))
    )
    (net (code "119") (name "unconnected-(J29-Pad14)") (class "Default")
      (node (ref "J29") (pin "14") (pinfunction "14_14") (pintype "passive"))
    )
    (net (code "120") (name "unconnected-(J29-Pad15)") (class "Default")
      (node (ref "J29") (pin "15") (pinfunction "15_15") (pintype "passive"))
    )
    (net (code "121") (name "unconnected-(J29-Pad16)") (class "Default")
      (node (ref "J29") (pin "16") (pinfunction "16_16") (pintype "passive"))
    )
    (net (code "122") (name "unconnected-(J29-Pad17)") (class "Default")
      (node (ref "J29") (pin "17") (pinfunction "17_17") (pintype "passive"))
    )
    (net (code "123") (name "unconnected-(J29-Pad18)") (class "Default")
      (node (ref "J29") (pin "18") (pinfunction "18_18") (pintype "passive"))
    )
    (net (code "124") (name "unconnected-(J29-Pad19)") (class "Default")
      (node (ref "J29") (pin "19") (pinfunction "19_19") (pintype "passive"))
    )
    (net (code "125") (name "unconnected-(J29-Pad20)") (class "Default")
      (node (ref "J29") (pin "20") (pinfunction "20_20") (pintype "passive"))
    )
    (net (code "126") (name "unconnected-(J30-Pad1)") (class "Default")
      (node (ref "J30") (pin "1") (pinfunction "1_1") (pintype "passive"))
    )
    (net (code "127") (name "unconnected-(J30-Pad2)") (class "Default")
      (node (ref "J30") (pin "2") (pinfunction "2_2") (pintype "passive"))
    )
    (net (code "128") (name "unconnected-(J30-Pad3)") (class "Default")
      (node (ref "J30") (pin "3") (pinfunction "3_3") (pintype "passive"))
    )
    (net (code "129") (name "unconnected-(J30-Pad4)") (class "Default")
      (node (ref "J30") (pin "4") (pinfunction "4_4") (pintype "passive"))
    )
    (net (code "130") (name "unconnected-(J30-Pad5)") (class "Default")
      (node (ref "J30") (pin "5") (pinfunction "5_5") (pintype "passive"))
    )
    (net (code "131") (name "unconnected-(J30-Pad6)") (class "Default")
      (node (ref "J30") (pin "6") (pinfunction "6_6") (pintype "passive"))
    )
    (net (code "132") (name "unconnected-(J30-Pad7)") (class "Default")
      (node (ref "J30") (pin "7") (pinfunction "7_7") (pintype "passive"))
    )
    (net (code "133") (name "unconnected-(J30-Pad8)") (class "Default")
      (node (ref "J30") (pin "8") (pinfunction "8_8") (pintype "passive"))
    )
    (net (code "134") (name "unconnected-(J30-Pad9)") (class "Default")
      (node (ref "J30") (pin "9") (pinfunction "9_9") (pintype "passive"))
    )
    (net (code "135") (name "unconnected-(J30-Pad10)") (class "Default")
      (node (ref "J30") (pin "10") (pinfunction "10_10") (pintype "passive"))
    )
    (net (code "136") (name "unconnected-(J30-Pad11)") (class "Default")
      (node (ref "J30") (pin "11") (pinfunction "11_11") (pintype "passive"))
    )
    (net (code "137") (name "unconnected-(J30-Pad12)") (class "Default")
      (node (ref "J30") (pin "12") (pinfunction "12_12") (pintype "passive"))
    )
    (net (code "138") (name "unconnected-(J30-Pad13)") (class "Default")
      (node (ref "J30") (pin "13") (pinfunction "13_13") (pintype "passive"))
    )
    (net (code "139") (name "unconnected-(J30-Pad14)") (class "Default")
      (node (ref "J30") (pin "14") (pinfunction "14_14") (pintype "passive"))
    )
    (net (code "140") (name "unconnected-(J30-Pad15)") (class "Default")
      (node (ref "J30") (pin "15") (pinfunction "15_15") (pintype "passive"))
    )
    (net (code "141") (name "unconnected-(J30-Pad16)") (class "Default")
      (node (ref "J30") (pin "16") (pinfunction "16_16") (pintype "passive"))
    )
    (net (code "142") (name "unconnected-(J30-Pad17)") (class "Default")
      (node (ref "J30") (pin "17") (pinfunction "17_17") (pintype "passive"))
    )
    (net (code "143") (name "unconnected-(J30-Pad18)") (class "Default")
      (node (ref "J30") (pin "18") (pinfunction "18_18") (pintype "passive"))
    )
    (net (code "144") (name "unconnected-(J30-Pad19)") (class "Default")
      (node (ref "J30") (pin "19") (pinfunction "19_19") (pintype "passive"))
    )
    (net (code "145") (name "unconnected-(J30-Pad20)") (class "Default")
      (node (ref "J30") (pin "20") (pinfunction "20_20") (pintype "passive"))
    )
    (net (code "146") (name "unconnected-(J40-Pad1)") (class "Default")
      (node (ref "J40") (pin "1") (pinfunction "1_1") (pintype "passive"))
    )
    (net (code "147") (name "unconnected-(J40-Pad2)") (class "Default")
      (node (ref "J40") (pin "2") (pinfunction "2_2") (pintype "passive"))
    )
    (net (code "148") (name "unconnected-(J40-Pad3)") (class "Default")
      (node (ref "J40") (pin "3") (pinfunction "3_3") (pintype "passive"))
    )
    (net (code "149") (name "unconnected-(J40-Pad4)") (class "Default")
      (node (ref "J40") (pin "4") (pinfunction "4_4") (pintype "passive"))
    )
    (net (code "150") (name "unconnected-(J40-Pad5)") (class "Default")
      (node (ref "J40") (pin "5") (pinfunction "5_5") (pintype "passive"))
    )
    (net (code "151") (name "unconnected-(J40-Pad6)") (class "Default")
      (node (ref "J40") (pin "6") (pinfunction "6_6") (pintype "passive"))
    )
    (net (code "152") (name "unconnected-(J40-Pad7)") (class "Default")
      (node (ref "J40") (pin "7") (pinfunction "7_7") (pintype "passive"))
    )
    (net (code "153") (name "unconnected-(J40-Pad8)") (class "Default")
      (node (ref "J40") (pin "8") (pinfunction "8_8") (pintype "passive"))
    )
    (net (code "154") (name "unconnected-(J40-Pad9)") (class "Default")
      (node (ref "J40") (pin "9") (pinfunction "9_9") (pintype "passive"))
    )
    (net (code "155") (name "unconnected-(J40-Pad10)") (class "Default")
      (node (ref "J40") (pin "10") (pinfunction "10_10") (pintype "passive"))
    )
    (net (code "156") (name "unconnected-(J40-Pad11)") (class "Default")
      (node (ref "J40") (pin "11") (pinfunction "11_11") (pintype "passive"))
    )
    (net (code "157") (name "unconnected-(J40-Pad12)") (class "Default")
      (node (ref "J40") (pin "12") (pinfunction "12_12") (pintype "passive"))
    )
    (net (code "158") (name "unconnected-(STS_LED-BLUE-Pad4)") (class "Default")
      (node (ref "STS_LED") (pin "4") (pinfunction "BLUE_4") (pintype "bidirectional"))
    )
    (net (code "159") (name "unconnected-(U1-AREF-Pad20)") (class "Default")
      (node (ref "U1") (pin "20") (pinfunction "AREF_20") (pintype "bidirectional"))
    )
    (net (code "160") (name "unconnected-(U1-PB6(XTAL1{slash}TOSC1)-Pad7)") (class "Default")
      (node (ref "U1") (pin "7") (pinfunction "PB6(XTAL1/TOSC1)_7") (pintype "bidirectional"))
    )
    (net (code "161") (name "unconnected-(U1-PB7(XTAL2{slash}TOSC2)-Pad8)") (class "Default")
      (node (ref "U1") (pin "8") (pinfunction "PB7(XTAL2/TOSC2)_8") (pintype "bidirectional"))
    )
  )
)
